# UI_BUTTON_LED.net
KiCad netlist of a schematic drawn in Altium Designer
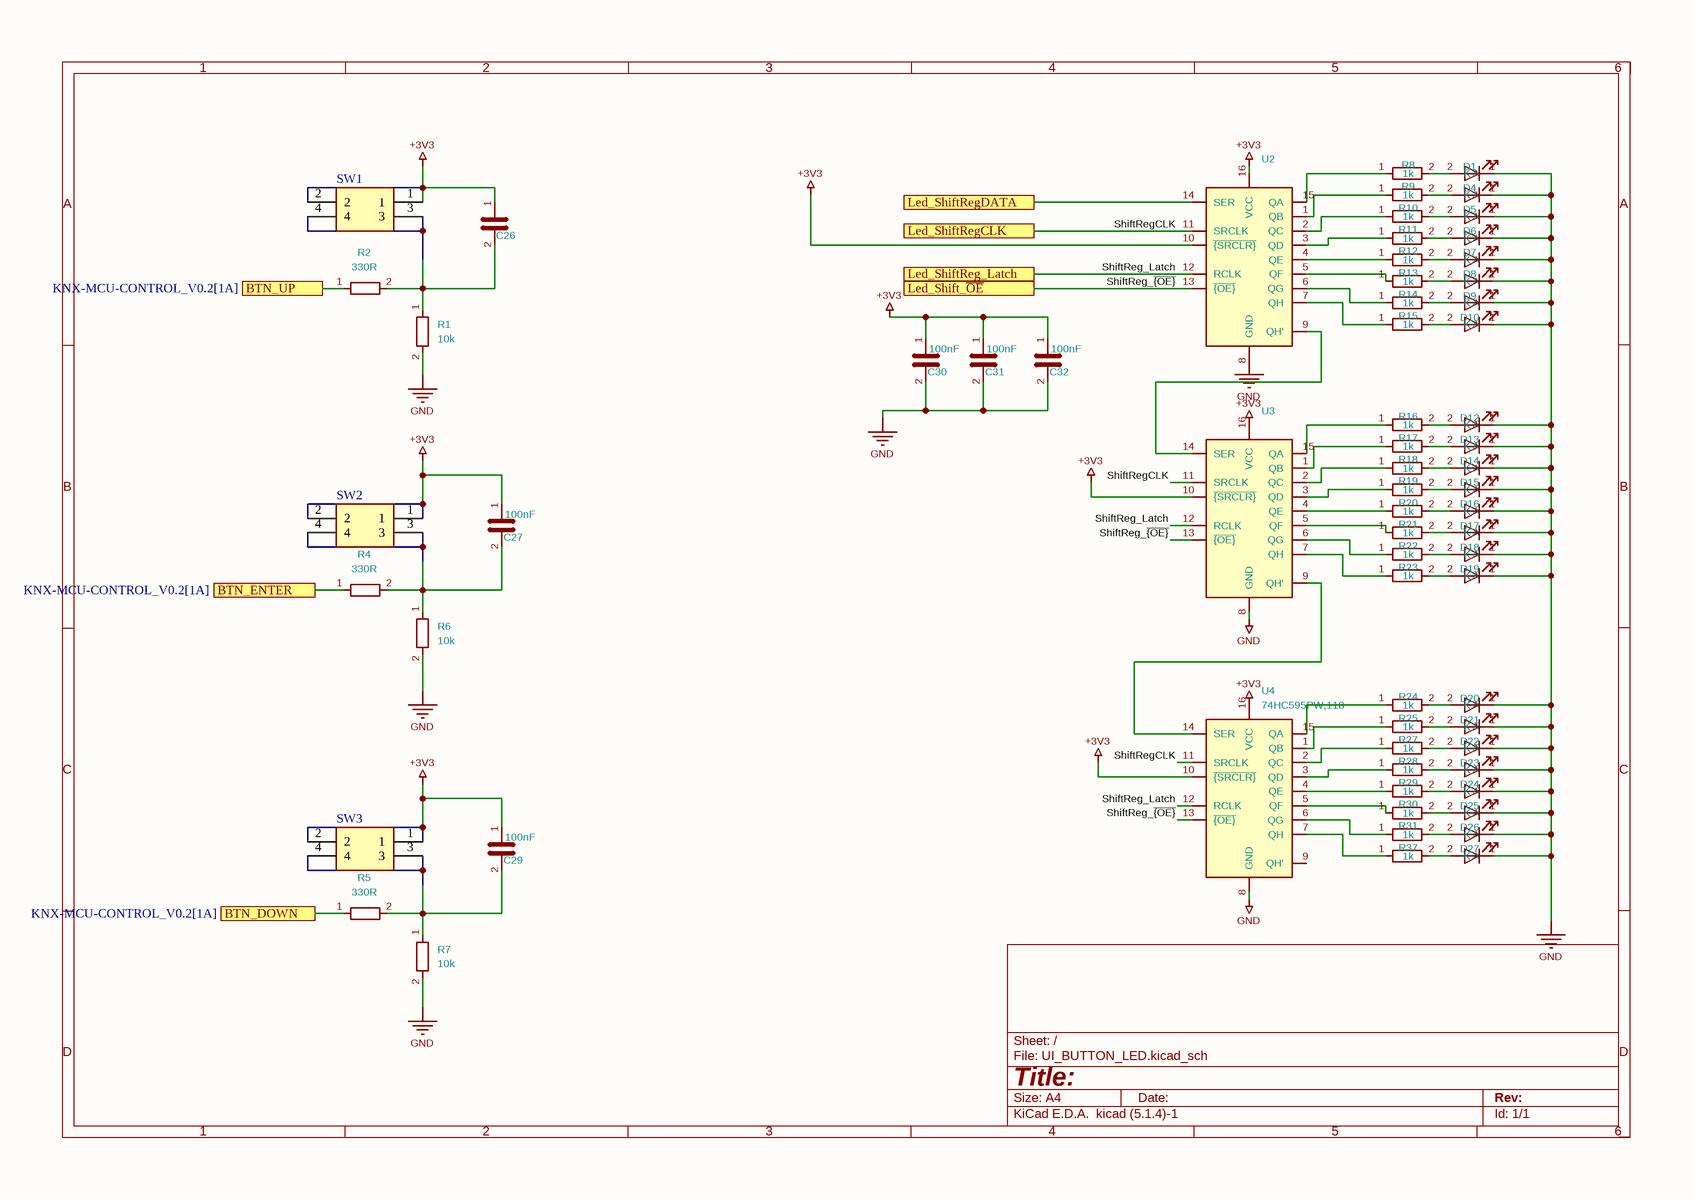
[diagram p0: UI_BUTTON_LED.SchDoc]

(export (version "E")
  (design (tool "Eeschema 10.0.6"))
  (components
    (comp (ref "C26")
      (value "100nF")
      (footprint "C_0603_1608Metric")
      (fields
        (field (name "MANUFACTURER PART NUMBER") "CC0603KRX7R9BB104")
        (field (name "MANUFACTURER") "YAGEO")
      )
      (libsource (lib "*") (part "C_3"))
    )
    (comp (ref "C27")
      (value "100nF")
      (footprint "C_0603_1608Metric")
      (fields
        (field (name "MANUFACTURER PART NUMBER") "CC0603KRX7R9BB104")
        (field (name "MANUFACTURER") "YAGEO")
      )
      (libsource (lib "*") (part "C_3"))
    )
    (comp (ref "C29")
      (value "100nF")
      (footprint "C_0603_1608Metric")
      (fields
        (field (name "MANUFACTURER PART NUMBER") "CC0603KRX7R9BB104")
        (field (name "MANUFACTURER") "YAGEO")
      )
      (libsource (lib "*") (part "C_3"))
    )
    (comp (ref "C30")
      (value "100nF")
      (footprint "C_0603_1608Metric")
      (fields
        (field (name "MANUFACTURER PART NUMBER") "CC0603KRX7R9BB104")
        (field (name "MANUFACTURER") "YAGEO")
      )
      (libsource (lib "*") (part "C_1"))
    )
    (comp (ref "C31")
      (value "100nF")
      (footprint "C_0603_1608Metric")
      (fields
        (field (name "MANUFACTURER PART NUMBER") "CC0603KRX7R9BB104")
        (field (name "MANUFACTURER") "YAGEO")
      )
      (libsource (lib "*") (part "C_1"))
    )
    (comp (ref "C32")
      (value "100nF")
      (footprint "C_0603_1608Metric")
      (fields
        (field (name "MANUFACTURER PART NUMBER") "CC0603KRX7R9BB104")
        (field (name "MANUFACTURER") "YAGEO")
      )
      (libsource (lib "*") (part "C_1"))
    )
    (comp (ref "D1")
      (value "LED")
      (footprint "LED_0603_1608Metric")
      (fields
        (field (name "MANUFACTURER") "LITEON")
        (field (name "MANUFACTURER PART NUMBER") "LTST-C190KFKT-5A")
      )
      (libsource (lib "Device") (part "LED"))
    )
    (comp (ref "D4")
      (value "LED")
      (footprint "LED_0603_1608Metric")
      (fields
        (field (name "MANUFACTURER") "LITEON")
        (field (name "MANUFACTURER PART NUMBER") "LTST-C190KFKT-5A")
      )
      (libsource (lib "Device") (part "LED"))
    )
    (comp (ref "D5")
      (value "LED")
      (footprint "LED_0603_1608Metric")
      (fields
        (field (name "MANUFACTURER") "LITEON")
        (field (name "MANUFACTURER PART NUMBER") "LTST-C190KFKT-5A")
      )
      (libsource (lib "Device") (part "LED"))
    )
    (comp (ref "D6")
      (value "LED")
      (footprint "LED_0603_1608Metric")
      (fields
        (field (name "MANUFACTURER") "LITEON")
        (field (name "MANUFACTURER PART NUMBER") "LTST-C190KFKT-5A")
      )
      (libsource (lib "Device") (part "LED"))
    )
    (comp (ref "D7")
      (value "LED")
      (footprint "LED_0603_1608Metric")
      (fields
        (field (name "MANUFACTURER") "LITEON")
        (field (name "MANUFACTURER PART NUMBER") "LTST-C190KFKT-5A")
      )
      (libsource (lib "Device") (part "LED"))
    )
    (comp (ref "D8")
      (value "LED")
      (footprint "LED_0603_1608Metric")
      (fields
        (field (name "MANUFACTURER") "LITEON")
        (field (name "MANUFACTURER PART NUMBER") "LTST-C190KFKT-5A")
      )
      (libsource (lib "Device") (part "LED"))
    )
    (comp (ref "D9")
      (value "LED")
      (footprint "LED_0603_1608Metric")
      (fields
        (field (name "MANUFACTURER") "LITEON")
        (field (name "MANUFACTURER PART NUMBER") "LTST-C190KFKT-5A")
      )
      (libsource (lib "Device") (part "LED"))
    )
    (comp (ref "D10")
      (value "LED")
      (footprint "LED_0603_1608Metric")
      (fields
        (field (name "MANUFACTURER") "LITEON")
        (field (name "MANUFACTURER PART NUMBER") "LTST-C190KFKT-5A")
      )
      (libsource (lib "Device") (part "LED"))
    )
    (comp (ref "D12")
      (value "LED")
      (footprint "LED_0603_1608Metric")
      (fields
        (field (name "MANUFACTURER") "LITEON")
        (field (name "MANUFACTURER PART NUMBER") "LTST-C190KFKT-5A")
      )
      (libsource (lib "Device") (part "LED"))
    )
    (comp (ref "D13")
      (value "LED")
      (footprint "LED_0603_1608Metric")
      (fields
        (field (name "MANUFACTURER") "LITEON")
        (field (name "MANUFACTURER PART NUMBER") "LTST-C190KFKT-5A")
      )
      (libsource (lib "Device") (part "LED"))
    )
    (comp (ref "D14")
      (value "LED")
      (footprint "LED_0603_1608Metric")
      (fields
        (field (name "MANUFACTURER") "LITEON")
        (field (name "MANUFACTURER PART NUMBER") "LTST-C190KFKT-5A")
      )
      (libsource (lib "Device") (part "LED"))
    )
    (comp (ref "D15")
      (value "LED")
      (footprint "LED_0603_1608Metric")
      (fields
        (field (name "MANUFACTURER") "LITEON")
        (field (name "MANUFACTURER PART NUMBER") "LTST-C190KFKT-5A")
      )
      (libsource (lib "Device") (part "LED"))
    )
    (comp (ref "D16")
      (value "LED")
      (footprint "LED_0603_1608Metric")
      (fields
        (field (name "MANUFACTURER") "LITEON")
        (field (name "MANUFACTURER PART NUMBER") "LTST-C190KFKT-5A")
      )
      (libsource (lib "Device") (part "LED"))
    )
    (comp (ref "D17")
      (value "LED")
      (footprint "LED_0603_1608Metric")
      (fields
        (field (name "MANUFACTURER") "LITEON")
        (field (name "MANUFACTURER PART NUMBER") "LTST-C190KFKT-5A")
      )
      (libsource (lib "Device") (part "LED"))
    )
    (comp (ref "D18")
      (value "LED")
      (footprint "LED_0603_1608Metric")
      (fields
        (field (name "MANUFACTURER") "LITEON")
        (field (name "MANUFACTURER PART NUMBER") "LTST-C190KFKT-5A")
      )
      (libsource (lib "Device") (part "LED"))
    )
    (comp (ref "D19")
      (value "LED")
      (footprint "LED_0603_1608Metric")
      (fields
        (field (name "MANUFACTURER") "LITEON")
        (field (name "MANUFACTURER PART NUMBER") "LTST-C190KFKT-5A")
      )
      (libsource (lib "Device") (part "LED"))
    )
    (comp (ref "D20")
      (value "LED")
      (footprint "LED_0603_1608Metric")
      (fields
        (field (name "MANUFACTURER") "LITEON")
        (field (name "MANUFACTURER PART NUMBER") "LTST-C190KFKT-5A")
      )
      (libsource (lib "Device") (part "LED"))
    )
    (comp (ref "D21")
      (value "LED")
      (footprint "LED_0603_1608Metric")
      (fields
        (field (name "MANUFACTURER") "LITEON")
        (field (name "MANUFACTURER PART NUMBER") "LTST-C190KFKT-5A")
      )
      (libsource (lib "Device") (part "LED"))
    )
    (comp (ref "D22")
      (value "LED")
      (footprint "LED_0603_1608Metric")
      (fields
        (field (name "MANUFACTURER") "LITEON")
        (field (name "MANUFACTURER PART NUMBER") "LTST-C190KFKT-5A")
      )
      (libsource (lib "Device") (part "LED"))
    )
    (comp (ref "D23")
      (value "LED")
      (footprint "LED_0603_1608Metric")
      (fields
        (field (name "MANUFACTURER") "LITEON")
        (field (name "MANUFACTURER PART NUMBER") "LTST-C190KFKT-5A")
      )
      (libsource (lib "Device") (part "LED"))
    )
    (comp (ref "D24")
      (value "LED")
      (footprint "LED_0603_1608Metric")
      (fields
        (field (name "MANUFACTURER") "LITEON")
        (field (name "MANUFACTURER PART NUMBER") "LTST-C190KFKT-5A")
      )
      (libsource (lib "Device") (part "LED"))
    )
    (comp (ref "D25")
      (value "LED")
      (footprint "LED_0603_1608Metric")
      (fields
        (field (name "MANUFACTURER") "LITEON")
        (field (name "MANUFACTURER PART NUMBER") "LTST-C190KFKT-5A")
      )
      (libsource (lib "Device") (part "LED"))
    )
    (comp (ref "D26")
      (value "LED")
      (footprint "LED_0603_1608Metric")
      (fields
        (field (name "MANUFACTURER") "LITEON")
        (field (name "MANUFACTURER PART NUMBER") "LTST-C190KFKT-5A")
      )
      (libsource (lib "Device") (part "LED"))
    )
    (comp (ref "D27")
      (value "LED")
      (footprint "LED_0603_1608Metric")
      (fields
        (field (name "MANUFACTURER") "LITEON")
        (field (name "MANUFACTURER PART NUMBER") "LTST-C190KFKT-5A")
      )
      (libsource (lib "Device") (part "LED"))
    )
    (comp (ref "R1")
      (value "10k")
      (footprint "R_0603_1608Metric")
      (fields (field (name "MANUFACTURER") "FOJAN") (field (name "MANUFACTURER PART NUMBER") "FRC0603J103TS"))
      (libsource (lib "") (part "R_1"))
    )
    (comp (ref "R2")
      (value "330R")
      (footprint "R_0603_1608Metric")
      (fields
        (field (name "MANUFACTURER") "FOJAN")
        (field (name "MANUFACTURER PART NUMBER") "FRC0603J331 TS")
      )
      (libsource (lib "Device") (part "R"))
    )
    (comp (ref "R4")
      (value "330R")
      (footprint "R_0603_1608Metric")
      (fields
        (field (name "MANUFACTURER") "FOJAN")
        (field (name "MANUFACTURER PART NUMBER") "FRC0603J331 TS")
      )
      (libsource (lib "Device") (part "R"))
    )
    (comp (ref "R5")
      (value "330R")
      (footprint "R_0603_1608Metric")
      (fields
        (field (name "MANUFACTURER") "FOJAN")
        (field (name "MANUFACTURER PART NUMBER") "FRC0603J331 TS")
      )
      (libsource (lib "Device") (part "R"))
    )
    (comp (ref "R6")
      (value "10k")
      (footprint "R_0603_1608Metric")
      (fields (field (name "MANUFACTURER") "FOJAN") (field (name "MANUFACTURER PART NUMBER") "FRC0603J103TS"))
      (libsource (lib "") (part "R_1"))
    )
    (comp (ref "R7")
      (value "10k")
      (footprint "R_0603_1608Metric")
      (fields (field (name "MANUFACTURER") "FOJAN") (field (name "MANUFACTURER PART NUMBER") "FRC0603J103TS"))
      (libsource (lib "") (part "R_1"))
    )
    (comp (ref "R8")
      (value "1k")
      (footprint "R_0603_1608Metric")
      (fields
        (field (name "MANUFACTURER") "YAGEO")
        (field (name "MANUFACTURER PART NUMBER") "RC0603JR-071KL")
      )
      (libsource (lib "Device") (part "R"))
    )
    (comp (ref "R9")
      (value "1k")
      (footprint "R_0603_1608Metric")
      (fields
        (field (name "MANUFACTURER") "YAGEO")
        (field (name "MANUFACTURER PART NUMBER") "RC0603JR-071KL")
      )
      (libsource (lib "Device") (part "R"))
    )
    (comp (ref "R10")
      (value "1k")
      (footprint "R_0603_1608Metric")
      (fields
        (field (name "MANUFACTURER") "YAGEO")
        (field (name "MANUFACTURER PART NUMBER") "RC0603JR-071KL")
      )
      (libsource (lib "Device") (part "R"))
    )
    (comp (ref "R11")
      (value "1k")
      (footprint "R_0603_1608Metric")
      (fields
        (field (name "MANUFACTURER") "YAGEO")
        (field (name "MANUFACTURER PART NUMBER") "RC0603JR-071KL")
      )
      (libsource (lib "Device") (part "R"))
    )
    (comp (ref "R12")
      (value "1k")
      (footprint "R_0603_1608Metric")
      (fields
        (field (name "MANUFACTURER") "YAGEO")
        (field (name "MANUFACTURER PART NUMBER") "RC0603JR-071KL")
      )
      (libsource (lib "Device") (part "R"))
    )
    (comp (ref "R13")
      (value "1k")
      (footprint "R_0603_1608Metric")
      (fields
        (field (name "MANUFACTURER") "YAGEO")
        (field (name "MANUFACTURER PART NUMBER") "RC0603JR-071KL")
      )
      (libsource (lib "Device") (part "R"))
    )
    (comp (ref "R14")
      (value "1k")
      (footprint "R_0603_1608Metric")
      (fields
        (field (name "MANUFACTURER") "YAGEO")
        (field (name "MANUFACTURER PART NUMBER") "RC0603JR-071KL")
      )
      (libsource (lib "Device") (part "R"))
    )
    (comp (ref "R15")
      (value "1k")
      (footprint "R_0603_1608Metric")
      (fields
        (field (name "MANUFACTURER") "YAGEO")
        (field (name "MANUFACTURER PART NUMBER") "RC0603JR-071KL")
      )
      (libsource (lib "Device") (part "R"))
    )
    (comp (ref "R16")
      (value "1k")
      (footprint "R_0603_1608Metric")
      (fields
        (field (name "MANUFACTURER") "YAGEO")
        (field (name "MANUFACTURER PART NUMBER") "RC0603JR-071KL")
      )
      (libsource (lib "Device") (part "R"))
    )
    (comp (ref "R17")
      (value "1k")
      (footprint "R_0603_1608Metric")
      (fields
        (field (name "MANUFACTURER") "YAGEO")
        (field (name "MANUFACTURER PART NUMBER") "RC0603JR-071KL")
      )
      (libsource (lib "Device") (part "R"))
    )
    (comp (ref "R18")
      (value "1k")
      (footprint "R_0603_1608Metric")
      (fields
        (field (name "MANUFACTURER") "YAGEO")
        (field (name "MANUFACTURER PART NUMBER") "RC0603JR-071KL")
      )
      (libsource (lib "Device") (part "R"))
    )
    (comp (ref "R19")
      (value "1k")
      (footprint "R_0603_1608Metric")
      (fields
        (field (name "MANUFACTURER") "YAGEO")
        (field (name "MANUFACTURER PART NUMBER") "RC0603JR-071KL")
      )
      (libsource (lib "Device") (part "R"))
    )
    (comp (ref "R20")
      (value "1k")
      (footprint "R_0603_1608Metric")
      (fields
        (field (name "MANUFACTURER") "YAGEO")
        (field (name "MANUFACTURER PART NUMBER") "RC0603JR-071KL")
      )
      (libsource (lib "Device") (part "R"))
    )
    (comp (ref "R21")
      (value "1k")
      (footprint "R_0603_1608Metric")
      (fields
        (field (name "MANUFACTURER") "YAGEO")
        (field (name "MANUFACTURER PART NUMBER") "RC0603JR-071KL")
      )
      (libsource (lib "Device") (part "R"))
    )
    (comp (ref "R22")
      (value "1k")
      (footprint "R_0603_1608Metric")
      (fields
        (field (name "MANUFACTURER") "YAGEO")
        (field (name "MANUFACTURER PART NUMBER") "RC0603JR-071KL")
      )
      (libsource (lib "Device") (part "R"))
    )
    (comp (ref "R23")
      (value "1k")
      (footprint "R_0603_1608Metric")
      (fields
        (field (name "MANUFACTURER") "YAGEO")
        (field (name "MANUFACTURER PART NUMBER") "RC0603JR-071KL")
      )
      (libsource (lib "Device") (part "R"))
    )
    (comp (ref "R24")
      (value "1k")
      (footprint "R_0603_1608Metric")
      (fields
        (field (name "MANUFACTURER") "YAGEO")
        (field (name "MANUFACTURER PART NUMBER") "RC0603JR-071KL")
      )
      (libsource (lib "Device") (part "R"))
    )
    (comp (ref "R25")
      (value "1k")
      (footprint "R_0603_1608Metric")
      (fields
        (field (name "MANUFACTURER") "YAGEO")
        (field (name "MANUFACTURER PART NUMBER") "RC0603JR-071KL")
      )
      (libsource (lib "Device") (part "R"))
    )
    (comp (ref "R27")
      (value "1k")
      (footprint "R_0603_1608Metric")
      (fields
        (field (name "MANUFACTURER") "YAGEO")
        (field (name "MANUFACTURER PART NUMBER") "RC0603JR-071KL")
      )
      (libsource (lib "Device") (part "R"))
    )
    (comp (ref "R28")
      (value "1k")
      (footprint "R_0603_1608Metric")
      (fields
        (field (name "MANUFACTURER") "YAGEO")
        (field (name "MANUFACTURER PART NUMBER") "RC0603JR-071KL")
      )
      (libsource (lib "Device") (part "R"))
    )
    (comp (ref "R29")
      (value "1k")
      (footprint "R_0603_1608Metric")
      (fields
        (field (name "MANUFACTURER") "YAGEO")
        (field (name "MANUFACTURER PART NUMBER") "RC0603JR-071KL")
      )
      (libsource (lib "Device") (part "R"))
    )
    (comp (ref "R30")
      (value "1k")
      (footprint "R_0603_1608Metric")
      (fields
        (field (name "MANUFACTURER") "YAGEO")
        (field (name "MANUFACTURER PART NUMBER") "RC0603JR-071KL")
      )
      (libsource (lib "Device") (part "R"))
    )
    (comp (ref "R31")
      (value "1k")
      (footprint "R_0603_1608Metric")
      (fields
        (field (name "MANUFACTURER") "YAGEO")
        (field (name "MANUFACTURER PART NUMBER") "RC0603JR-071KL")
      )
      (libsource (lib "Device") (part "R"))
    )
    (comp (ref "R37")
      (value "1k")
      (footprint "R_0603_1608Metric")
      (fields
        (field (name "MANUFACTURER") "YAGEO")
        (field (name "MANUFACTURER PART NUMBER") "RC0603JR-071KL")
      )
      (libsource (lib "Device") (part "R"))
    )
    (comp (ref "SW1")
      (value "TSA06141-225B532CA-3C00")
      (footprint "SamacSys:TL1105")
      (description "Through Hole-4P,8.2x7.6mm")
      (fields (field (name "MANUFACTURER") "Khon"))
      (libsource (lib "*") (part "TL1105BF160Q"))
    )
    (comp (ref "SW2")
      (value "TSA06141-225B532CA-3C00")
      (footprint "SamacSys:TL1105")
      (description "Through Hole-4P,8.2x7.6mm")
      (fields (field (name "MANUFACTURER") "Khon"))
      (libsource (lib "*") (part "TL1105BF160Q"))
    )
    (comp (ref "SW3")
      (value "TSA06141-225B532CA-3C00")
      (footprint "SamacSys:TL1105")
      (description "Through Hole-4P,8.2x7.6mm")
      (fields (field (name "MANUFACTURER") "Khon"))
      (libsource (lib "*") (part "TL1105BF160Q"))
    )
    (comp (ref "U2")
      (value "74HC595PW,118")
      (footprint "TSSOP-16_4.4x5mm_P0.65mm")
      (fields (field (name "MANUFACTURER") "Nexperia"))
      (libsource (lib "74xx") (part "74HC595"))
    )
    (comp (ref "U3")
      (value "74HC595PW,118")
      (footprint "TSSOP-16_4.4x5mm_P0.65mm")
      (fields (field (name "MANUFACTURER") "Nexperia"))
      (libsource (lib "74xx") (part "74HC595"))
    )
    (comp (ref "U4")
      (value "74HC595PW,118")
      (footprint "TSSOP-16_4.4x5mm_P0.65mm")
      (fields (field (name "MANUFACTURER") "Nexperia"))
      (libsource (lib "74xx") (part "74HC595"))
    )
  )
  (nets
    (net (code "1") (name "+3V3") (class "Default")
      (node (ref "C26") (pin "1") (pinfunction "1_1") (pintype "passive"))
      (node (ref "C27") (pin "1") (pinfunction "1_1") (pintype "passive"))
      (node (ref "C29") (pin "1") (pinfunction "1_1") (pintype "passive"))
      (node (ref "C30") (pin "1") (pinfunction "1_1") (pintype "passive"))
      (node (ref "C31") (pin "1") (pinfunction "1_1") (pintype "passive"))
      (node (ref "C32") (pin "1") (pinfunction "1_1") (pintype "passive"))
      (node (ref "SW1") (pin "1") (pinfunction "1_1") (pintype "passive"))
      (node (ref "SW1") (pin "2") (pinfunction "2_2") (pintype "passive"))
      (node (ref "SW2") (pin "1") (pinfunction "1_1") (pintype "passive"))
      (node (ref "SW2") (pin "2") (pinfunction "2_2") (pintype "passive"))
      (node (ref "SW3") (pin "1") (pinfunction "1_1") (pintype "passive"))
      (node (ref "SW3") (pin "2") (pinfunction "2_2") (pintype "passive"))
      (node (ref "U2") (pin "10") (pinfunction "~{{SRCLR}}_10") (pintype "passive"))
      (node (ref "U2") (pin "16") (pinfunction "VCC_16") (pintype "passive"))
      (node (ref "U3") (pin "10") (pinfunction "~{{SRCLR}}_10") (pintype "passive"))
      (node (ref "U3") (pin "16") (pinfunction "VCC_16") (pintype "passive"))
      (node (ref "U4") (pin "10") (pinfunction "~{{SRCLR}}_10") (pintype "passive"))
      (node (ref "U4") (pin "16") (pinfunction "VCC_16") (pintype "passive"))
    )
    (net (code "2") (name "/BTN_DOWN") (class "Default")
      (node (ref "R5") (pin "1") (pinfunction "1_1") (pintype "passive"))
    )
    (net (code "3") (name "/BTN_ENTER") (class "Default")
      (node (ref "R4") (pin "1") (pinfunction "1_1") (pintype "passive"))
    )
    (net (code "4") (name "/BTN_UP") (class "Default")
      (node (ref "R2") (pin "1") (pinfunction "1_1") (pintype "passive"))
    )
    (net (code "5") (name "/Led_ShiftRegDATA") (class "Default")
      (node (ref "U2") (pin "14") (pinfunction "SER_14") (pintype "passive"))
    )
    (net (code "6") (name "/ShiftRegCLK") (class "Default")
      (node (ref "U2") (pin "11") (pinfunction "SRCLK_11") (pintype "passive"))
      (node (ref "U3") (pin "11") (pinfunction "SRCLK_11") (pintype "passive"))
      (node (ref "U4") (pin "11") (pinfunction "SRCLK_11") (pintype "passive"))
    )
    (net (code "7") (name "/ShiftReg_Latch") (class "Default")
      (node (ref "U2") (pin "12") (pinfunction "RCLK_12") (pintype "passive"))
      (node (ref "U3") (pin "12") (pinfunction "RCLK_12") (pintype "passive"))
      (node (ref "U4") (pin "12") (pinfunction "RCLK_12") (pintype "passive"))
    )
    (net (code "8") (name "/ShiftReg_~{{OE}}") (class "Default")
      (node (ref "U2") (pin "13") (pinfunction "~{{OE}}_13") (pintype "passive"))
      (node (ref "U3") (pin "13") (pinfunction "~{{OE}}_13") (pintype "passive"))
      (node (ref "U4") (pin "13") (pinfunction "~{{OE}}_13") (pintype "passive"))
    )
    (net (code "9") (name "GND") (class "Default")
      (node (ref "C30") (pin "2") (pinfunction "2_2") (pintype "passive"))
      (node (ref "C31") (pin "2") (pinfunction "2_2") (pintype "passive"))
      (node (ref "C32") (pin "2") (pinfunction "2_2") (pintype "passive"))
      (node (ref "D1") (pin "1") (pinfunction "K_1") (pintype "passive"))
      (node (ref "D10") (pin "1") (pinfunction "K_1") (pintype "passive"))
      (node (ref "D12") (pin "1") (pinfunction "K_1") (pintype "passive"))
      (node (ref "D13") (pin "1") (pinfunction "K_1") (pintype "passive"))
      (node (ref "D14") (pin "1") (pinfunction "K_1") (pintype "passive"))
      (node (ref "D15") (pin "1") (pinfunction "K_1") (pintype "passive"))
      (node (ref "D16") (pin "1") (pinfunction "K_1") (pintype "passive"))
      (node (ref "D17") (pin "1") (pinfunction "K_1") (pintype "passive"))
      (node (ref "D18") (pin "1") (pinfunction "K_1") (pintype "passive"))
      (node (ref "D19") (pin "1") (pinfunction "K_1") (pintype "passive"))
      (node (ref "D20") (pin "1") (pinfunction "K_1") (pintype "passive"))
      (node (ref "D21") (pin "1") (pinfunction "K_1") (pintype "passive"))
      (node (ref "D22") (pin "1") (pinfunction "K_1") (pintype "passive"))
      (node (ref "D23") (pin "1") (pinfunction "K_1") (pintype "passive"))
      (node (ref "D24") (pin "1") (pinfunction "K_1") (pintype "passive"))
      (node (ref "D25") (pin "1") (pinfunction "K_1") (pintype "passive"))
      (node (ref "D26") (pin "1") (pinfunction "K_1") (pintype "passive"))
      (node (ref "D27") (pin "1") (pinfunction "K_1") (pintype "passive"))
      (node (ref "D4") (pin "1") (pinfunction "K_1") (pintype "passive"))
      (node (ref "D5") (pin "1") (pinfunction "K_1") (pintype "passive"))
      (node (ref "D6") (pin "1") (pinfunction "K_1") (pintype "passive"))
      (node (ref "D7") (pin "1") (pinfunction "K_1") (pintype "passive"))
      (node (ref "D8") (pin "1") (pinfunction "K_1") (pintype "passive"))
      (node (ref "D9") (pin "1") (pinfunction "K_1") (pintype "passive"))
      (node (ref "R1") (pin "2") (pinfunction "2_2") (pintype "passive"))
      (node (ref "R6") (pin "2") (pinfunction "2_2") (pintype "passive"))
      (node (ref "R7") (pin "2") (pinfunction "2_2") (pintype "passive"))
      (node (ref "U2") (pin "8") (pinfunction "GND_8") (pintype "passive"))
      (node (ref "U3") (pin "8") (pinfunction "GND_8") (pintype "passive"))
      (node (ref "U4") (pin "8") (pinfunction "GND_8") (pintype "passive"))
    )
    (net (code "10") (name "Net-(C26-Pad2)") (class "Default")
      (node (ref "C26") (pin "2") (pinfunction "2_2") (pintype "passive"))
      (node (ref "R1") (pin "1") (pinfunction "1_1") (pintype "passive"))
      (node (ref "R2") (pin "2") (pinfunction "2_2") (pintype "passive"))
      (node (ref "SW1") (pin "3") (pinfunction "3_3") (pintype "passive"))
      (node (ref "SW1") (pin "4") (pinfunction "4_4") (pintype "passive"))
    )
    (net (code "11") (name "Net-(C27-Pad2)") (class "Default")
      (node (ref "C27") (pin "2") (pinfunction "2_2") (pintype "passive"))
      (node (ref "R4") (pin "2") (pinfunction "2_2") (pintype "passive"))
      (node (ref "R6") (pin "1") (pinfunction "1_1") (pintype "passive"))
      (node (ref "SW2") (pin "3") (pinfunction "3_3") (pintype "passive"))
      (node (ref "SW2") (pin "4") (pinfunction "4_4") (pintype "passive"))
    )
    (net (code "12") (name "Net-(C29-Pad2)") (class "Default")
      (node (ref "C29") (pin "2") (pinfunction "2_2") (pintype "passive"))
      (node (ref "R5") (pin "2") (pinfunction "2_2") (pintype "passive"))
      (node (ref "R7") (pin "1") (pinfunction "1_1") (pintype "passive"))
      (node (ref "SW3") (pin "3") (pinfunction "3_3") (pintype "passive"))
      (node (ref "SW3") (pin "4") (pinfunction "4_4") (pintype "passive"))
    )
    (net (code "13") (name "Net-(D1-A)") (class "Default")
      (node (ref "D1") (pin "2") (pinfunction "A_2") (pintype "passive"))
      (node (ref "R8") (pin "2") (pinfunction "2_2") (pintype "passive"))
    )
    (net (code "14") (name "Net-(D4-A)") (class "Default")
      (node (ref "D4") (pin "2") (pinfunction "A_2") (pintype "passive"))
      (node (ref "R9") (pin "2") (pinfunction "2_2") (pintype "passive"))
    )
    (net (code "15") (name "Net-(D5-A)") (class "Default")
      (node (ref "D5") (pin "2") (pinfunction "A_2") (pintype "passive"))
      (node (ref "R10") (pin "2") (pinfunction "2_2") (pintype "passive"))
    )
    (net (code "16") (name "Net-(D6-A)") (class "Default")
      (node (ref "D6") (pin "2") (pinfunction "A_2") (pintype "passive"))
      (node (ref "R11") (pin "2") (pinfunction "2_2") (pintype "passive"))
    )
    (net (code "17") (name "Net-(D7-A)") (class "Default")
      (node (ref "D7") (pin "2") (pinfunction "A_2") (pintype "passive"))
      (node (ref "R12") (pin "2") (pinfunction "2_2") (pintype "passive"))
    )
    (net (code "18") (name "Net-(D8-A)") (class "Default")
      (node (ref "D8") (pin "2") (pinfunction "A_2") (pintype "passive"))
      (node (ref "R13") (pin "2") (pinfunction "2_2") (pintype "passive"))
    )
    (net (code "19") (name "Net-(D9-A)") (class "Default")
      (node (ref "D9") (pin "2") (pinfunction "A_2") (pintype "passive"))
      (node (ref "R14") (pin "2") (pinfunction "2_2") (pintype "passive"))
    )
    (net (code "20") (name "Net-(D10-A)") (class "Default")
      (node (ref "D10") (pin "2") (pinfunction "A_2") (pintype "passive"))
      (node (ref "R15") (pin "2") (pinfunction "2_2") (pintype "passive"))
    )
    (net (code "21") (name "Net-(D12-A)") (class "Default")
      (node (ref "D12") (pin "2") (pinfunction "A_2") (pintype "passive"))
      (node (ref "R16") (pin "2") (pinfunction "2_2") (pintype "passive"))
    )
    (net (code "22") (name "Net-(D13-A)") (class "Default")
      (node (ref "D13") (pin "2") (pinfunction "A_2") (pintype "passive"))
      (node (ref "R17") (pin "2") (pinfunction "2_2") (pintype "passive"))
    )
    (net (code "23") (name "Net-(D14-A)") (class "Default")
      (node (ref "D14") (pin "2") (pinfunction "A_2") (pintype "passive"))
      (node (ref "R18") (pin "2") (pinfunction "2_2") (pintype "passive"))
    )
    (net (code "24") (name "Net-(D15-A)") (class "Default")
      (node (ref "D15") (pin "2") (pinfunction "A_2") (pintype "passive"))
      (node (ref "R19") (pin "2") (pinfunction "2_2") (pintype "passive"))
    )
    (net (code "25") (name "Net-(D16-A)") (class "Default")
      (node (ref "D16") (pin "2") (pinfunction "A_2") (pintype "passive"))
      (node (ref "R20") (pin "2") (pinfunction "2_2") (pintype "passive"))
    )
    (net (code "26") (name "Net-(D17-A)") (class "Default")
      (node (ref "D17") (pin "2") (pinfunction "A_2") (pintype "passive"))
      (node (ref "R21") (pin "2") (pinfunction "2_2") (pintype "passive"))
    )
    (net (code "27") (name "Net-(D18-A)") (class "Default")
      (node (ref "D18") (pin "2") (pinfunction "A_2") (pintype "passive"))
      (node (ref "R22") (pin "2") (pinfunction "2_2") (pintype "passive"))
    )
    (net (code "28") (name "Net-(D19-A)") (class "Default")
      (node (ref "D19") (pin "2") (pinfunction "A_2") (pintype "passive"))
      (node (ref "R23") (pin "2") (pinfunction "2_2") (pintype "passive"))
    )
    (net (code "29") (name "Net-(D20-A)") (class "Default")
      (node (ref "D20") (pin "2") (pinfunction "A_2") (pintype "passive"))
      (node (ref "R24") (pin "2") (pinfunction "2_2") (pintype "passive"))
    )
    (net (code "30") (name "Net-(D21-A)") (class "Default")
      (node (ref "D21") (pin "2") (pinfunction "A_2") (pintype "passive"))
      (node (ref "R25") (pin "2") (pinfunction "2_2") (pintype "passive"))
    )
    (net (code "31") (name "Net-(D22-A)") (class "Default")
      (node (ref "D22") (pin "2") (pinfunction "A_2") (pintype "passive"))
      (node (ref "R27") (pin "2") (pinfunction "2_2") (pintype "passive"))
    )
    (net (code "32") (name "Net-(D23-A)") (class "Default")
      (node (ref "D23") (pin "2") (pinfunction "A_2") (pintype "passive"))
      (node (ref "R28") (pin "2") (pinfunction "2_2") (pintype "passive"))
    )
    (net (code "33") (name "Net-(D24-A)") (class "Default")
      (node (ref "D24") (pin "2") (pinfunction "A_2") (pintype "passive"))
      (node (ref "R29") (pin "2") (pinfunction "2_2") (pintype "passive"))
    )
    (net (code "34") (name "Net-(D25-A)") (class "Default")
      (node (ref "D25") (pin "2") (pinfunction "A_2") (pintype "passive"))
      (node (ref "R30") (pin "2") (pinfunction "2_2") (pintype "passive"))
    )
    (net (code "35") (name "Net-(D26-A)") (class "Default")
      (node (ref "D26") (pin "2") (pinfunction "A_2") (pintype "passive"))
      (node (ref "R31") (pin "2") (pinfunction "2_2") (pintype "passive"))
    )
    (net (code "36") (name "Net-(D27-A)") (class "Default")
      (node (ref "D27") (pin "2") (pinfunction "A_2") (pintype "passive"))
      (node (ref "R37") (pin "2") (pinfunction "2_2") (pintype "passive"))
    )
    (net (code "37") (name "Net-(U2-QA)") (class "Default")
      (node (ref "R8") (pin "1") (pinfunction "1_1") (pintype "passive"))
      (node (ref "U2") (pin "15") (pinfunction "QA_15") (pintype "passive"))
    )
    (net (code "38") (name "Net-(U2-QB)") (class "Default")
      (node (ref "R9") (pin "1") (pinfunction "1_1") (pintype "passive"))
      (node (ref "U2") (pin "1") (pinfunction "QB_1") (pintype "passive"))
    )
    (net (code "39") (name "Net-(U2-QC)") (class "Default")
      (node (ref "R10") (pin "1") (pinfunction "1_1") (pintype "passive"))
      (node (ref "U2") (pin "2") (pinfunction "QC_2") (pintype "passive"))
    )
    (net (code "40") (name "Net-(U2-QD)") (class "Default")
      (node (ref "R11") (pin "1") (pinfunction "1_1") (pintype "passive"))
      (node (ref "U2") (pin "3") (pinfunction "QD_3") (pintype "passive"))
    )
    (net (code "41") (name "Net-(U2-QE)") (class "Default")
      (node (ref "R12") (pin "1") (pinfunction "1_1") (pintype "passive"))
      (node (ref "U2") (pin "4") (pinfunction "QE_4") (pintype "passive"))
    )
    (net (code "42") (name "Net-(U2-QF)") (class "Default")
      (node (ref "R13") (pin "1") (pinfunction "1_1") (pintype "passive"))
      (node (ref "U2") (pin "5") (pinfunction "QF_5") (pintype "passive"))
    )
    (net (code "43") (name "Net-(U2-QG)") (class "Default")
      (node (ref "R14") (pin "1") (pinfunction "1_1") (pintype "passive"))
      (node (ref "U2") (pin "6") (pinfunction "QG_6") (pintype "passive"))
    )
    (net (code "44") (name "Net-(U2-QH')") (class "Default")
      (node (ref "U2") (pin "9") (pinfunction "QH'_9") (pintype "passive"))
      (node (ref "U3") (pin "14") (pinfunction "SER_14") (pintype "passive"))
    )
    (net (code "45") (name "Net-(U2-QH)") (class "Default")
      (node (ref "R15") (pin "1") (pinfunction "1_1") (pintype "passive"))
      (node (ref "U2") (pin "7") (pinfunction "QH_7") (pintype "passive"))
    )
    (net (code "46") (name "Net-(U3-QA)") (class "Default")
      (node (ref "R16") (pin "1") (pinfunction "1_1") (pintype "passive"))
      (node (ref "U3") (pin "15") (pinfunction "QA_15") (pintype "passive"))
    )
    (net (code "47") (name "Net-(U3-QB)") (class "Default")
      (node (ref "R17") (pin "1") (pinfunction "1_1") (pintype "passive"))
      (node (ref "U3") (pin "1") (pinfunction "QB_1") (pintype "passive"))
    )
    (net (code "48") (name "Net-(U3-QC)") (class "Default")
      (node (ref "R18") (pin "1") (pinfunction "1_1") (pintype "passive"))
      (node (ref "U3") (pin "2") (pinfunction "QC_2") (pintype "passive"))
    )
    (net (code "49") (name "Net-(U3-QD)") (class "Default")
      (node (ref "R19") (pin "1") (pinfunction "1_1") (pintype "passive"))
      (node (ref "U3") (pin "3") (pinfunction "QD_3") (pintype "passive"))
    )
    (net (code "50") (name "Net-(U3-QE)") (class "Default")
      (node (ref "R20") (pin "1") (pinfunction "1_1") (pintype "passive"))
      (node (ref "U3") (pin "4") (pinfunction "QE_4") (pintype "passive"))
    )
    (net (code "51") (name "Net-(U3-QF)") (class "Default")
      (node (ref "R21") (pin "1") (pinfunction "1_1") (pintype "passive"))
      (node (ref "U3") (pin "5") (pinfunction "QF_5") (pintype "passive"))
    )
    (net (code "52") (name "Net-(U3-QG)") (class "Default")
      (node (ref "R22") (pin "1") (pinfunction "1_1") (pintype "passive"))
      (node (ref "U3") (pin "6") (pinfunction "QG_6") (pintype "passive"))
    )
    (net (code "53") (name "Net-(U3-QH')") (class "Default")
      (node (ref "U3") (pin "9") (pinfunction "QH'_9") (pintype "passive"))
      (node (ref "U4") (pin "14") (pinfunction "SER_14") (pintype "passive"))
    )
    (net (code "54") (name "Net-(U3-QH)") (class "Default")
      (node (ref "R23") (pin "1") (pinfunction "1_1") (pintype "passive"))
      (node (ref "U3") (pin "7") (pinfunction "QH_7") (pintype "passive"))
    )
    (net (code "55") (name "Net-(U4-QA)") (class "Default")
      (node (ref "R24") (pin "1") (pinfunction "1_1") (pintype "passive"))
      (node (ref "U4") (pin "15") (pinfunction "QA_15") (pintype "passive"))
    )
    (net (code "56") (name "Net-(U4-QB)") (class "Default")
      (node (ref "R25") (pin "1") (pinfunction "1_1") (pintype "passive"))
      (node (ref "U4") (pin "1") (pinfunction "QB_1") (pintype "passive"))
    )
    (net (code "57") (name "Net-(U4-QC)") (class "Default")
      (node (ref "R27") (pin "1") (pinfunction "1_1") (pintype "passive"))
      (node (ref "U4") (pin "2") (pinfunction "QC_2") (pintype "passive"))
    )
    (net (code "58") (name "Net-(U4-QD)") (class "Default")
      (node (ref "R28") (pin "1") (pinfunction "1_1") (pintype "passive"))
      (node (ref "U4") (pin "3") (pinfunction "QD_3") (pintype "passive"))
    )
    (net (code "59") (name "Net-(U4-QE)") (class "Default")
      (node (ref "R29") (pin "1") (pinfunction "1_1") (pintype "passive"))
      (node (ref "U4") (pin "4") (pinfunction "QE_4") (pintype "passive"))
    )
    (net (code "60") (name "Net-(U4-QF)") (class "Default")
      (node (ref "R30") (pin "1") (pinfunction "1_1") (pintype "passive"))
      (node (ref "U4") (pin "5") (pinfunction "QF_5") (pintype "passive"))
    )
    (net (code "61") (name "Net-(U4-QG)") (class "Default")
      (node (ref "R31") (pin "1") (pinfunction "1_1") (pintype "passive"))
      (node (ref "U4") (pin "6") (pinfunction "QG_6") (pintype "passive"))
    )
    (net (code "62") (name "Net-(U4-QH)") (class "Default")
      (node (ref "R37") (pin "1") (pinfunction "1_1") (pintype "passive"))
      (node (ref "U4") (pin "7") (pinfunction "QH_7") (pintype "passive"))
    )
    (net (code "63") (name "unconnected-(U4-QH'-Pad9)") (class "Default")
      (node (ref "U4") (pin "9") (pinfunction "QH'_9") (pintype "passive"))
    )
  )
)
